# minireg-lt8410.net
KiCad netlist of a schematic drawn in Altium Designer
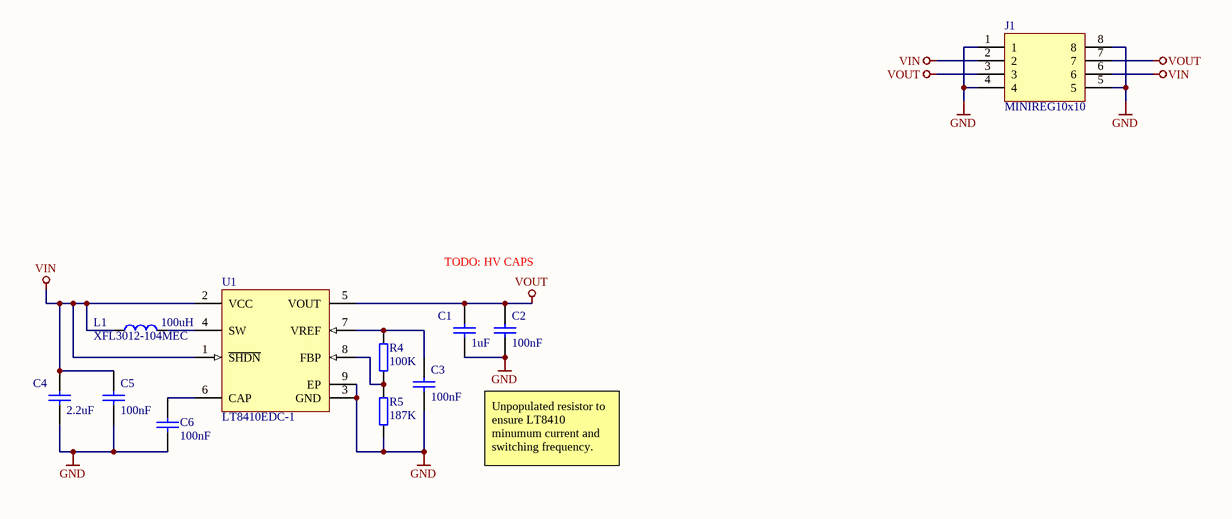
[diagram p0: minireg-lt8410.SchDoc]

(export (version "E")
  (design (tool "Eeschema 10.0.6"))
  (components
    (comp (ref "C1")
      (value "1uF")
      (footprint "CAP0603")
      (description "CAP SM 0603 X7R 1uF")
      (fields (field (name "PART NUMBER") "CAP-SM-0603-X7R-1uF") (field (name "MANUFACTURER") "GENERIC"))
      (libsource (lib "electronpowered") (part "CAP"))
    )
    (comp (ref "C2")
      (value "100nF")
      (footprint "CAP0603")
      (description "CAP SM 0603 X7R 100nF")
      (fields (field (name "PART NUMBER") "CAP-SM-0603-X7R-100nF") (field (name "MANUFACTURER") "GENERIC"))
      (libsource (lib "electronpowered") (part "CAP"))
    )
    (comp (ref "C3")
      (value "100nF")
      (footprint "CAP0603")
      (description "CAP SM 0603 X7R 100nF")
      (fields (field (name "PART NUMBER") "CAP-SM-0603-X7R-100nF") (field (name "MANUFACTURER") "GENERIC"))
      (libsource (lib "electronpowered") (part "CAP"))
    )
    (comp (ref "C4")
      (value "2.2uF")
      (footprint "CAP0603")
      (description "CAP SM 0603 X5R 2.2uF")
      (fields (field (name "PART NUMBER") "CAP-SM-0603-X5R-2.2uF") (field (name "MANUFACTURER") "GENERIC"))
      (libsource (lib "electronpowered") (part "CAP"))
    )
    (comp (ref "C5")
      (value "100nF")
      (footprint "CAP0603")
      (description "CAP SM 0603 X7R 100nF")
      (fields (field (name "PART NUMBER") "CAP-SM-0603-X7R-100nF") (field (name "MANUFACTURER") "GENERIC"))
      (libsource (lib "electronpowered") (part "CAP"))
    )
    (comp (ref "C6")
      (value "100nF")
      (footprint "CAP0603")
      (description "CAP SM 0603 X7R 100nF")
      (fields (field (name "PART NUMBER") "CAP-SM-0603-X7R-100nF") (field (name "MANUFACTURER") "GENERIC"))
      (libsource (lib "electronpowered") (part "CAP"))
    )
    (comp (ref "J1")
      (value "MINIREG10x10")
      (footprint "MINIREG8_10x10R")
      (libsource (lib "minireg") (part "MINIREG10x10"))
    )
    (comp (ref "L1")
      (value "XFL3012-104MEC")
      (footprint "XFL3012")
      (description "IND SM 100uH 290mA 3Ohm 1212 3x3mm")
      (fields (field (name "ALTIUM_VALUE") "100uH"))
      (libsource (lib "gpr") (part "XFL3012-104MEC"))
    )
    (comp (ref "R4")
      (value "100K")
      (footprint "RES0603")
      (description "RES SM 0603 100K")
      (fields (field (name "PART NUMBER") "RES-SM-0603-100K") (field (name "MANUFACTURER") "GENERIC"))
      (libsource (lib "electronpowered") (part "RES"))
    )
    (comp (ref "R5")
      (value "187K")
      (footprint "RES0603")
      (description "RES SM 0603 187K")
      (fields (field (name "PART NUMBER") "RES-SM-0603-187K") (field (name "MANUFACTURER") "GENERIC"))
      (libsource (lib "electronpowered") (part "RES"))
    )
    (comp (ref "U1")
      (value "LT8410EDC-1")
      (footprint "LT8410")
      (fields
        (field (name "MANUFACTURER") "Linear Technology")
        (field (name "PARTNUMBER") "LT8410EDC-1#TRMPBF")
      )
      (libsource (lib "gpr") (part "LT8410"))
    )
  )
  (nets
    (net (code "1") (name "GND") (class "Default")
      (node (ref "C1") (pin "1") (pinfunction "1_1") (pintype "passive"))
      (node (ref "C2") (pin "1") (pinfunction "1_1") (pintype "passive"))
      (node (ref "C3") (pin "1") (pinfunction "1_1") (pintype "passive"))
      (node (ref "C4") (pin "1") (pinfunction "1_1") (pintype "passive"))
      (node (ref "C5") (pin "1") (pinfunction "1_1") (pintype "passive"))
      (node (ref "C6") (pin "1") (pinfunction "1_1") (pintype "passive"))
      (node (ref "J1") (pin "1") (pinfunction "1_1") (pintype "power_in"))
      (node (ref "J1") (pin "4") (pinfunction "4_4") (pintype "power_in"))
      (node (ref "J1") (pin "5") (pinfunction "5_5") (pintype "power_in"))
      (node (ref "J1") (pin "8") (pinfunction "8_8") (pintype "power_in"))
      (node (ref "R5") (pin "1") (pinfunction "1_1") (pintype "passive"))
      (node (ref "U1") (pin "3") (pinfunction "GND_3") (pintype "power_in"))
      (node (ref "U1") (pin "9") (pinfunction "EP_9") (pintype "power_in"))
    )
    (net (code "2") (name "Net-(U1-CAP)") (class "Default")
      (node (ref "C6") (pin "2") (pinfunction "2_2") (pintype "passive"))
      (node (ref "U1") (pin "6") (pinfunction "CAP_6") (pintype "passive"))
    )
    (net (code "3") (name "Net-(U1-FBP)") (class "Default")
      (node (ref "R4") (pin "1") (pinfunction "1_1") (pintype "passive"))
      (node (ref "R5") (pin "2") (pinfunction "2_2") (pintype "passive"))
      (node (ref "U1") (pin "8") (pinfunction "FBP_8") (pintype "input"))
    )
    (net (code "4") (name "Net-(U1-SW)") (class "Default")
      (node (ref "L1") (pin "2") (pinfunction "2_2") (pintype "passive"))
      (node (ref "U1") (pin "4") (pinfunction "SW_4") (pintype "passive"))
    )
    (net (code "5") (name "Net-(U1-VREF)") (class "Default")
      (node (ref "C3") (pin "2") (pinfunction "2_2") (pintype "passive"))
      (node (ref "R4") (pin "2") (pinfunction "2_2") (pintype "passive"))
      (node (ref "U1") (pin "7") (pinfunction "VREF_7") (pintype "input"))
    )
    (net (code "6") (name "VIN") (class "Default")
      (node (ref "C4") (pin "2") (pinfunction "2_2") (pintype "passive"))
      (node (ref "C5") (pin "2") (pinfunction "2_2") (pintype "passive"))
      (node (ref "J1") (pin "2") (pinfunction "2_2") (pintype "power_in"))
      (node (ref "J1") (pin "6") (pinfunction "6_6") (pintype "power_in"))
      (node (ref "L1") (pin "1") (pinfunction "1_1") (pintype "passive"))
      (node (ref "U1") (pin "1") (pinfunction "~{SHDN}_1") (pintype "input"))
      (node (ref "U1") (pin "2") (pinfunction "VCC_2") (pintype "power_in"))
    )
    (net (code "7") (name "VOUT") (class "Default")
      (node (ref "C1") (pin "2") (pinfunction "2_2") (pintype "passive"))
      (node (ref "C2") (pin "2") (pinfunction "2_2") (pintype "passive"))
      (node (ref "J1") (pin "3") (pinfunction "3_3") (pintype "power_in"))
      (node (ref "J1") (pin "7") (pinfunction "7_7") (pintype "power_in"))
      (node (ref "U1") (pin "5") (pinfunction "VOUT_5") (pintype "power_in"))
    )
  )
)
